# Wilamowski.net
KiCad netlist of a schematic drawn in EAGLE
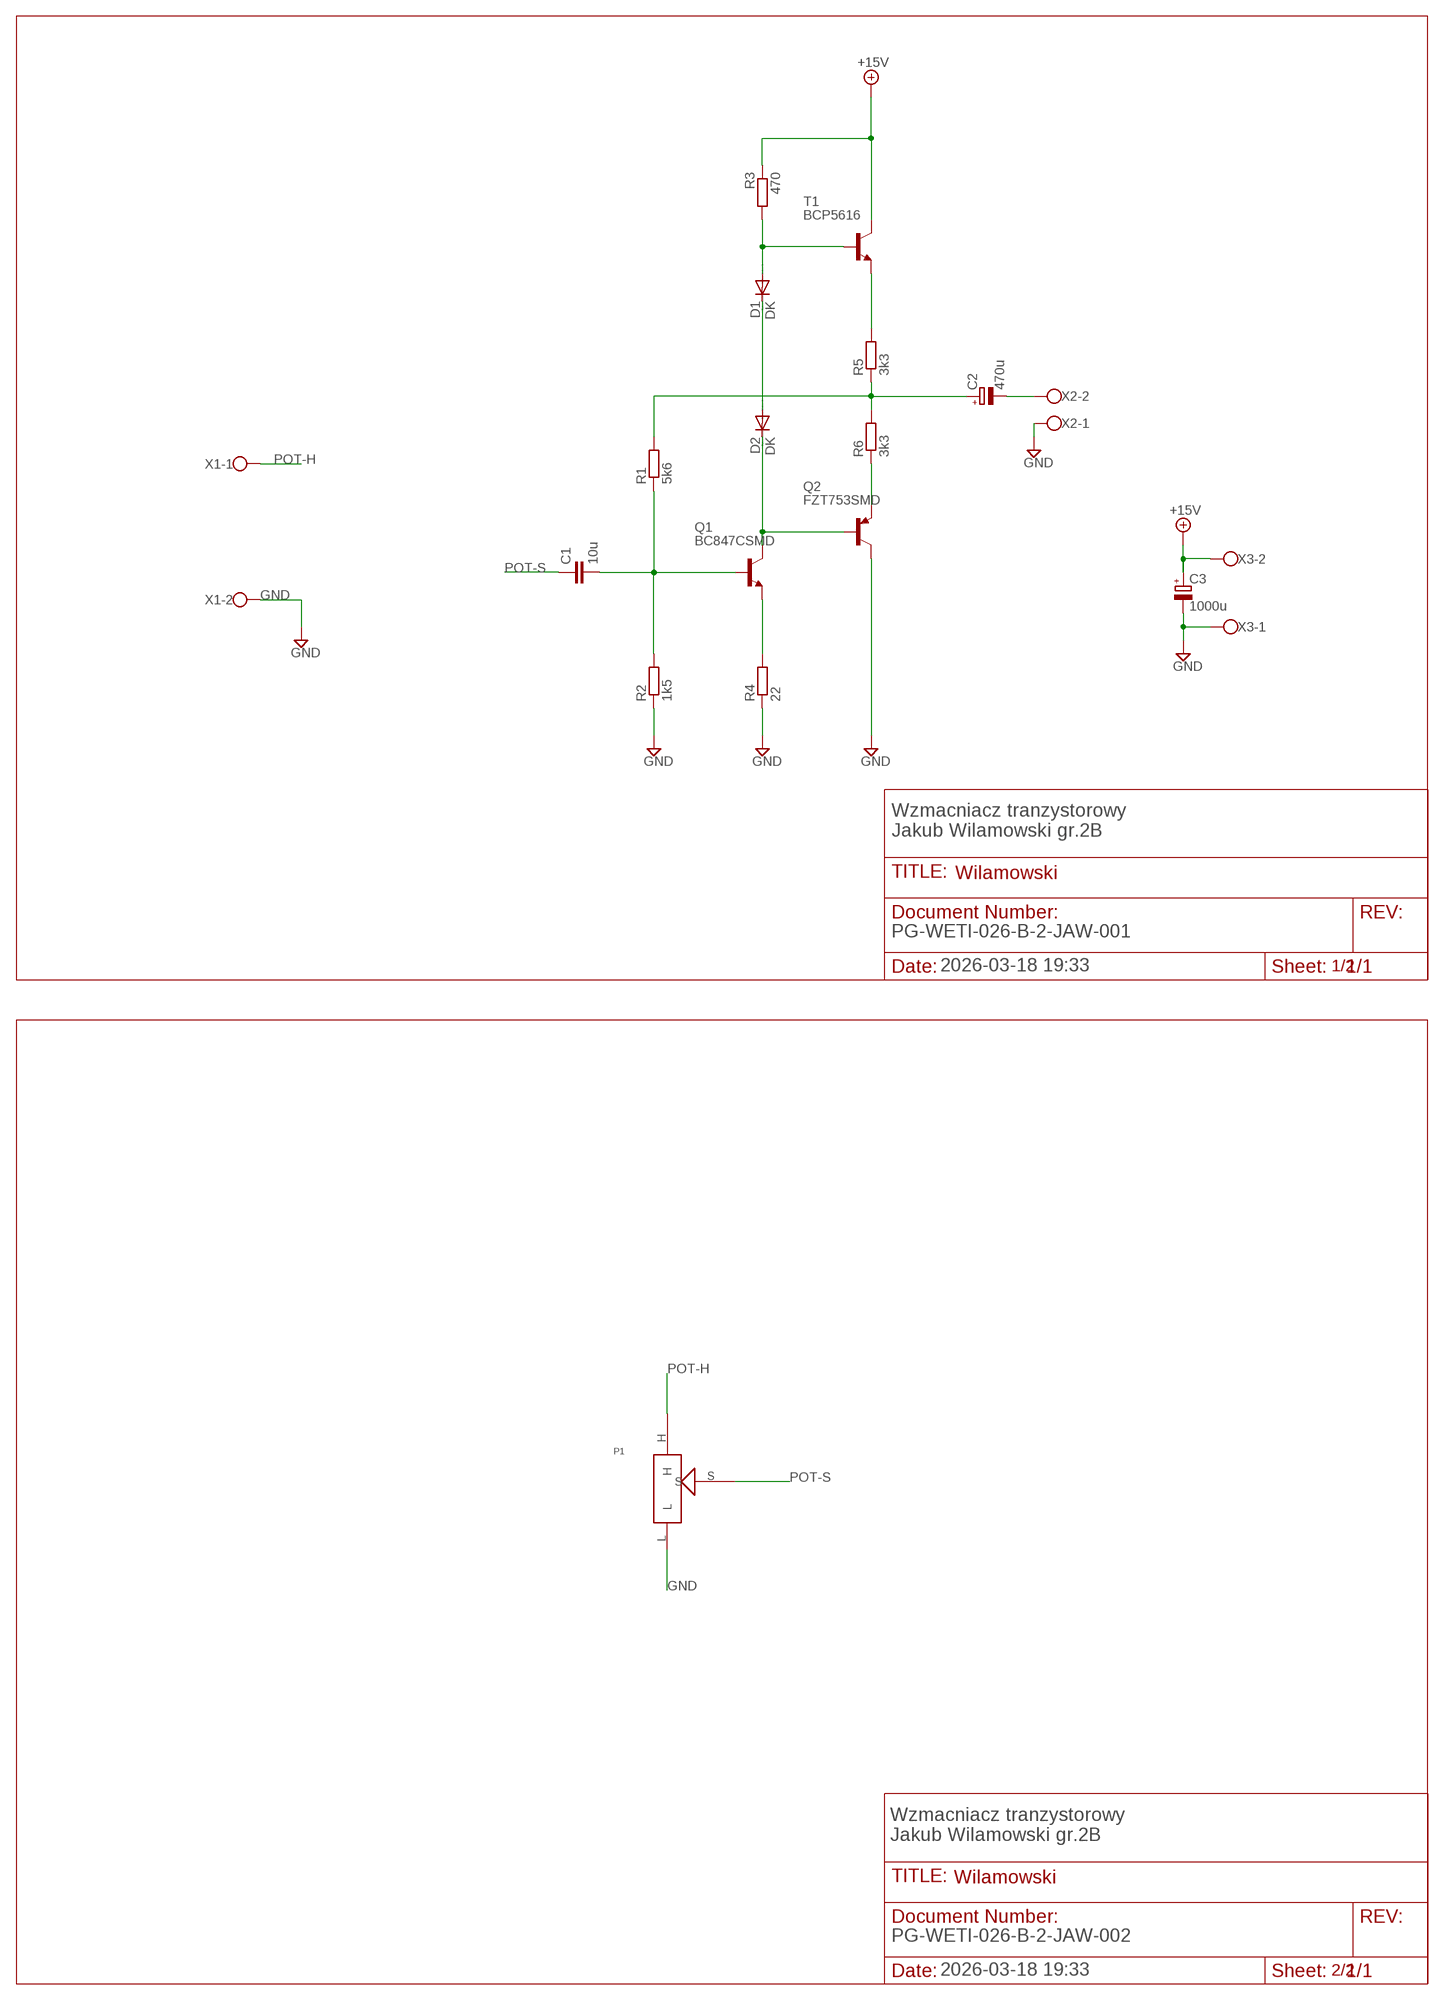
[diagram p0: schematic, sheet 1]

(export (version "E")
  (design (tool "Eeschema 10.0.6"))
  (components
    (comp (ref "C1")
      (value "10u")
      (footprint "eagle-import:C025-024X044")
      (libsource (lib "eagle-import") (part "C-EU025-024X044"))
    )
    (comp (ref "C2")
      (value "470u")
      (footprint "eagle-import:139CLL-3R")
      (libsource (lib "eagle-import") (part "CPOL-EU139CLL-3R"))
    )
    (comp (ref "C3")
      (value "1000u")
      (footprint "eagle-import:139CLL-3R")
      (libsource (lib "eagle-import") (part "CPOL-EU139CLL-3R"))
    )
    (comp (ref "D1")
      (value "DK")
      (footprint "eagle-import:SOD106-R")
      (libsource (lib "eagle-import") (part "DIODE-SOD106-R"))
    )
    (comp (ref "D2")
      (value "DK")
      (footprint "eagle-import:SOD106-R")
      (libsource (lib "eagle-import") (part "DIODE-SOD106-R"))
    )
    (comp (ref "P1")
      (value "POTENCJOMETRSMD")
      (footprint "eagle-import:1804(3314)")
      (libsource (lib "eagle-import") (part "POTENCJOMETRSMD"))
    )
    (comp (ref "Q1")
      (value "BC847CSMD")
      (footprint "eagle-import:SOT23")
      (libsource (lib "eagle-import") (part "BC847SMDC"))
    )
    (comp (ref "Q2")
      (value "FZT753SMD")
      (footprint "eagle-import:SOT223")
      (libsource (lib "eagle-import") (part "FZT753SMD"))
    )
    (comp (ref "R1")
      (value "5k6")
      (footprint "eagle-import:R2010")
      (libsource (lib "eagle-import") (part "R-EU_R2010"))
    )
    (comp (ref "R2")
      (value "1k5")
      (footprint "eagle-import:R2010")
      (libsource (lib "eagle-import") (part "R-EU_R2010"))
    )
    (comp (ref "R3")
      (value "470")
      (footprint "eagle-import:R2010")
      (libsource (lib "eagle-import") (part "R-EU_R2010"))
    )
    (comp (ref "R4")
      (value "22")
      (footprint "eagle-import:R2010")
      (libsource (lib "eagle-import") (part "R-EU_R2010"))
    )
    (comp (ref "R5")
      (value "3k3")
      (footprint "eagle-import:R2010")
      (libsource (lib "eagle-import") (part "R-EU_R2010"))
    )
    (comp (ref "R6")
      (value "3k3")
      (footprint "eagle-import:R2010")
      (libsource (lib "eagle-import") (part "R-EU_R2010"))
    )
    (comp (ref "T1")
      (value "BCP5616")
      (footprint "eagle-import:SOT223")
      (libsource (lib "eagle-import") (part "-NPN-SOT223"))
    )
    (comp (ref "X1")
      (value "W237-102")
      (footprint "eagle-import:W237-102")
      (fields (field (name "MPN") "237-102"))
      (libsource (lib "eagle-import") (part "W237-102"))
    )
    (comp (ref "X2")
      (value "W237-102")
      (footprint "eagle-import:W237-102")
      (fields (field (name "MPN") "237-102"))
      (libsource (lib "eagle-import") (part "W237-102"))
    )
    (comp (ref "X3")
      (value "W237-102")
      (footprint "eagle-import:W237-102")
      (fields (field (name "MPN") "237-102"))
      (libsource (lib "eagle-import") (part "W237-102"))
    )
  )
  (nets
    (net (code "1") (name "+15V") (class "Default")
      (node (ref "C3") (pin "+") (pinfunction "+_+") (pintype "passive"))
      (node (ref "R3") (pin "1") (pinfunction "1_1") (pintype "passive"))
      (node (ref "T1") (pin "4") (pinfunction "C_4") (pintype "passive"))
      (node (ref "X3") (pin "2") (pinfunction "KL_2") (pintype "passive"))
    )
    (net (code "2") (name "/POT-H") (class "Default")
      (node (ref "P1") (pin "H") (pinfunction "H_H") (pintype "bidirectional"))
      (node (ref "X1") (pin "1") (pinfunction "KL_1") (pintype "passive"))
    )
    (net (code "3") (name "/POT-S") (class "Default")
      (node (ref "C1") (pin "1") (pinfunction "1_1") (pintype "passive"))
      (node (ref "P1") (pin "S") (pinfunction "S_S") (pintype "bidirectional"))
    )
    (net (code "4") (name "GND") (class "Default")
      (node (ref "C3") (pin "-") (pinfunction "-_-") (pintype "passive"))
      (node (ref "P1") (pin "L") (pinfunction "L_L") (pintype "bidirectional"))
      (node (ref "Q2") (pin "2") (pinfunction "C_2") (pintype "passive"))
      (node (ref "Q2") (pin "4") (pinfunction "C_4") (pintype "passive"))
      (node (ref "R2") (pin "1") (pinfunction "1_1") (pintype "passive"))
      (node (ref "R4") (pin "1") (pinfunction "1_1") (pintype "passive"))
      (node (ref "X1") (pin "2") (pinfunction "KL_2") (pintype "passive"))
      (node (ref "X2") (pin "1") (pinfunction "KL_1") (pintype "passive"))
      (node (ref "X3") (pin "1") (pinfunction "KL_1") (pintype "passive"))
    )
    (net (code "5") (name "Net-(C2-Pad+)") (class "Default")
      (node (ref "C2") (pin "+") (pinfunction "+_+") (pintype "passive"))
      (node (ref "R1") (pin "2") (pinfunction "2_2") (pintype "passive"))
      (node (ref "R5") (pin "1") (pinfunction "1_1") (pintype "passive"))
      (node (ref "R6") (pin "2") (pinfunction "2_2") (pintype "passive"))
    )
    (net (code "6") (name "Net-(D1-PadC)") (class "Default")
      (node (ref "D1") (pin "C") (pinfunction "C_C") (pintype "passive"))
      (node (ref "D2") (pin "A") (pinfunction "A_A") (pintype "passive"))
    )
    (net (code "7") (name "Net-(Q1-B)") (class "Default")
      (node (ref "C1") (pin "2") (pinfunction "2_2") (pintype "passive"))
      (node (ref "Q1") (pin "1") (pinfunction "B_1") (pintype "passive"))
      (node (ref "R1") (pin "1") (pinfunction "1_1") (pintype "passive"))
      (node (ref "R2") (pin "2") (pinfunction "2_2") (pintype "passive"))
    )
    (net (code "8") (name "Net-(Q1-C)") (class "Default")
      (node (ref "D2") (pin "C") (pinfunction "C_C") (pintype "passive"))
      (node (ref "Q1") (pin "3") (pinfunction "C_3") (pintype "passive"))
      (node (ref "Q2") (pin "1") (pinfunction "B_1") (pintype "passive"))
    )
    (net (code "9") (name "Net-(Q1-E)") (class "Default")
      (node (ref "Q1") (pin "2") (pinfunction "E_2") (pintype "passive"))
      (node (ref "R4") (pin "2") (pinfunction "2_2") (pintype "passive"))
    )
    (net (code "10") (name "Net-(Q2-E)") (class "Default")
      (node (ref "Q2") (pin "3") (pinfunction "E_3") (pintype "passive"))
      (node (ref "R6") (pin "1") (pinfunction "1_1") (pintype "passive"))
    )
    (net (code "11") (name "Net-(T1-B)") (class "Default")
      (node (ref "D1") (pin "A") (pinfunction "A_A") (pintype "passive"))
      (node (ref "R3") (pin "2") (pinfunction "2_2") (pintype "passive"))
      (node (ref "T1") (pin "1") (pinfunction "B_1") (pintype "passive"))
    )
    (net (code "12") (name "Net-(T1-E)") (class "Default")
      (node (ref "R5") (pin "2") (pinfunction "2_2") (pintype "passive"))
      (node (ref "T1") (pin "3") (pinfunction "E_3") (pintype "passive"))
    )
    (net (code "13") (name "Net-(X2B-KL)") (class "Default")
      (node (ref "C2") (pin "-") (pinfunction "-_-") (pintype "passive"))
      (node (ref "X2") (pin "2") (pinfunction "KL_2") (pintype "passive"))
    )
  )
)
